# GS_02_Core.net
KiCad netlist of a schematic drawn in Altium Designer
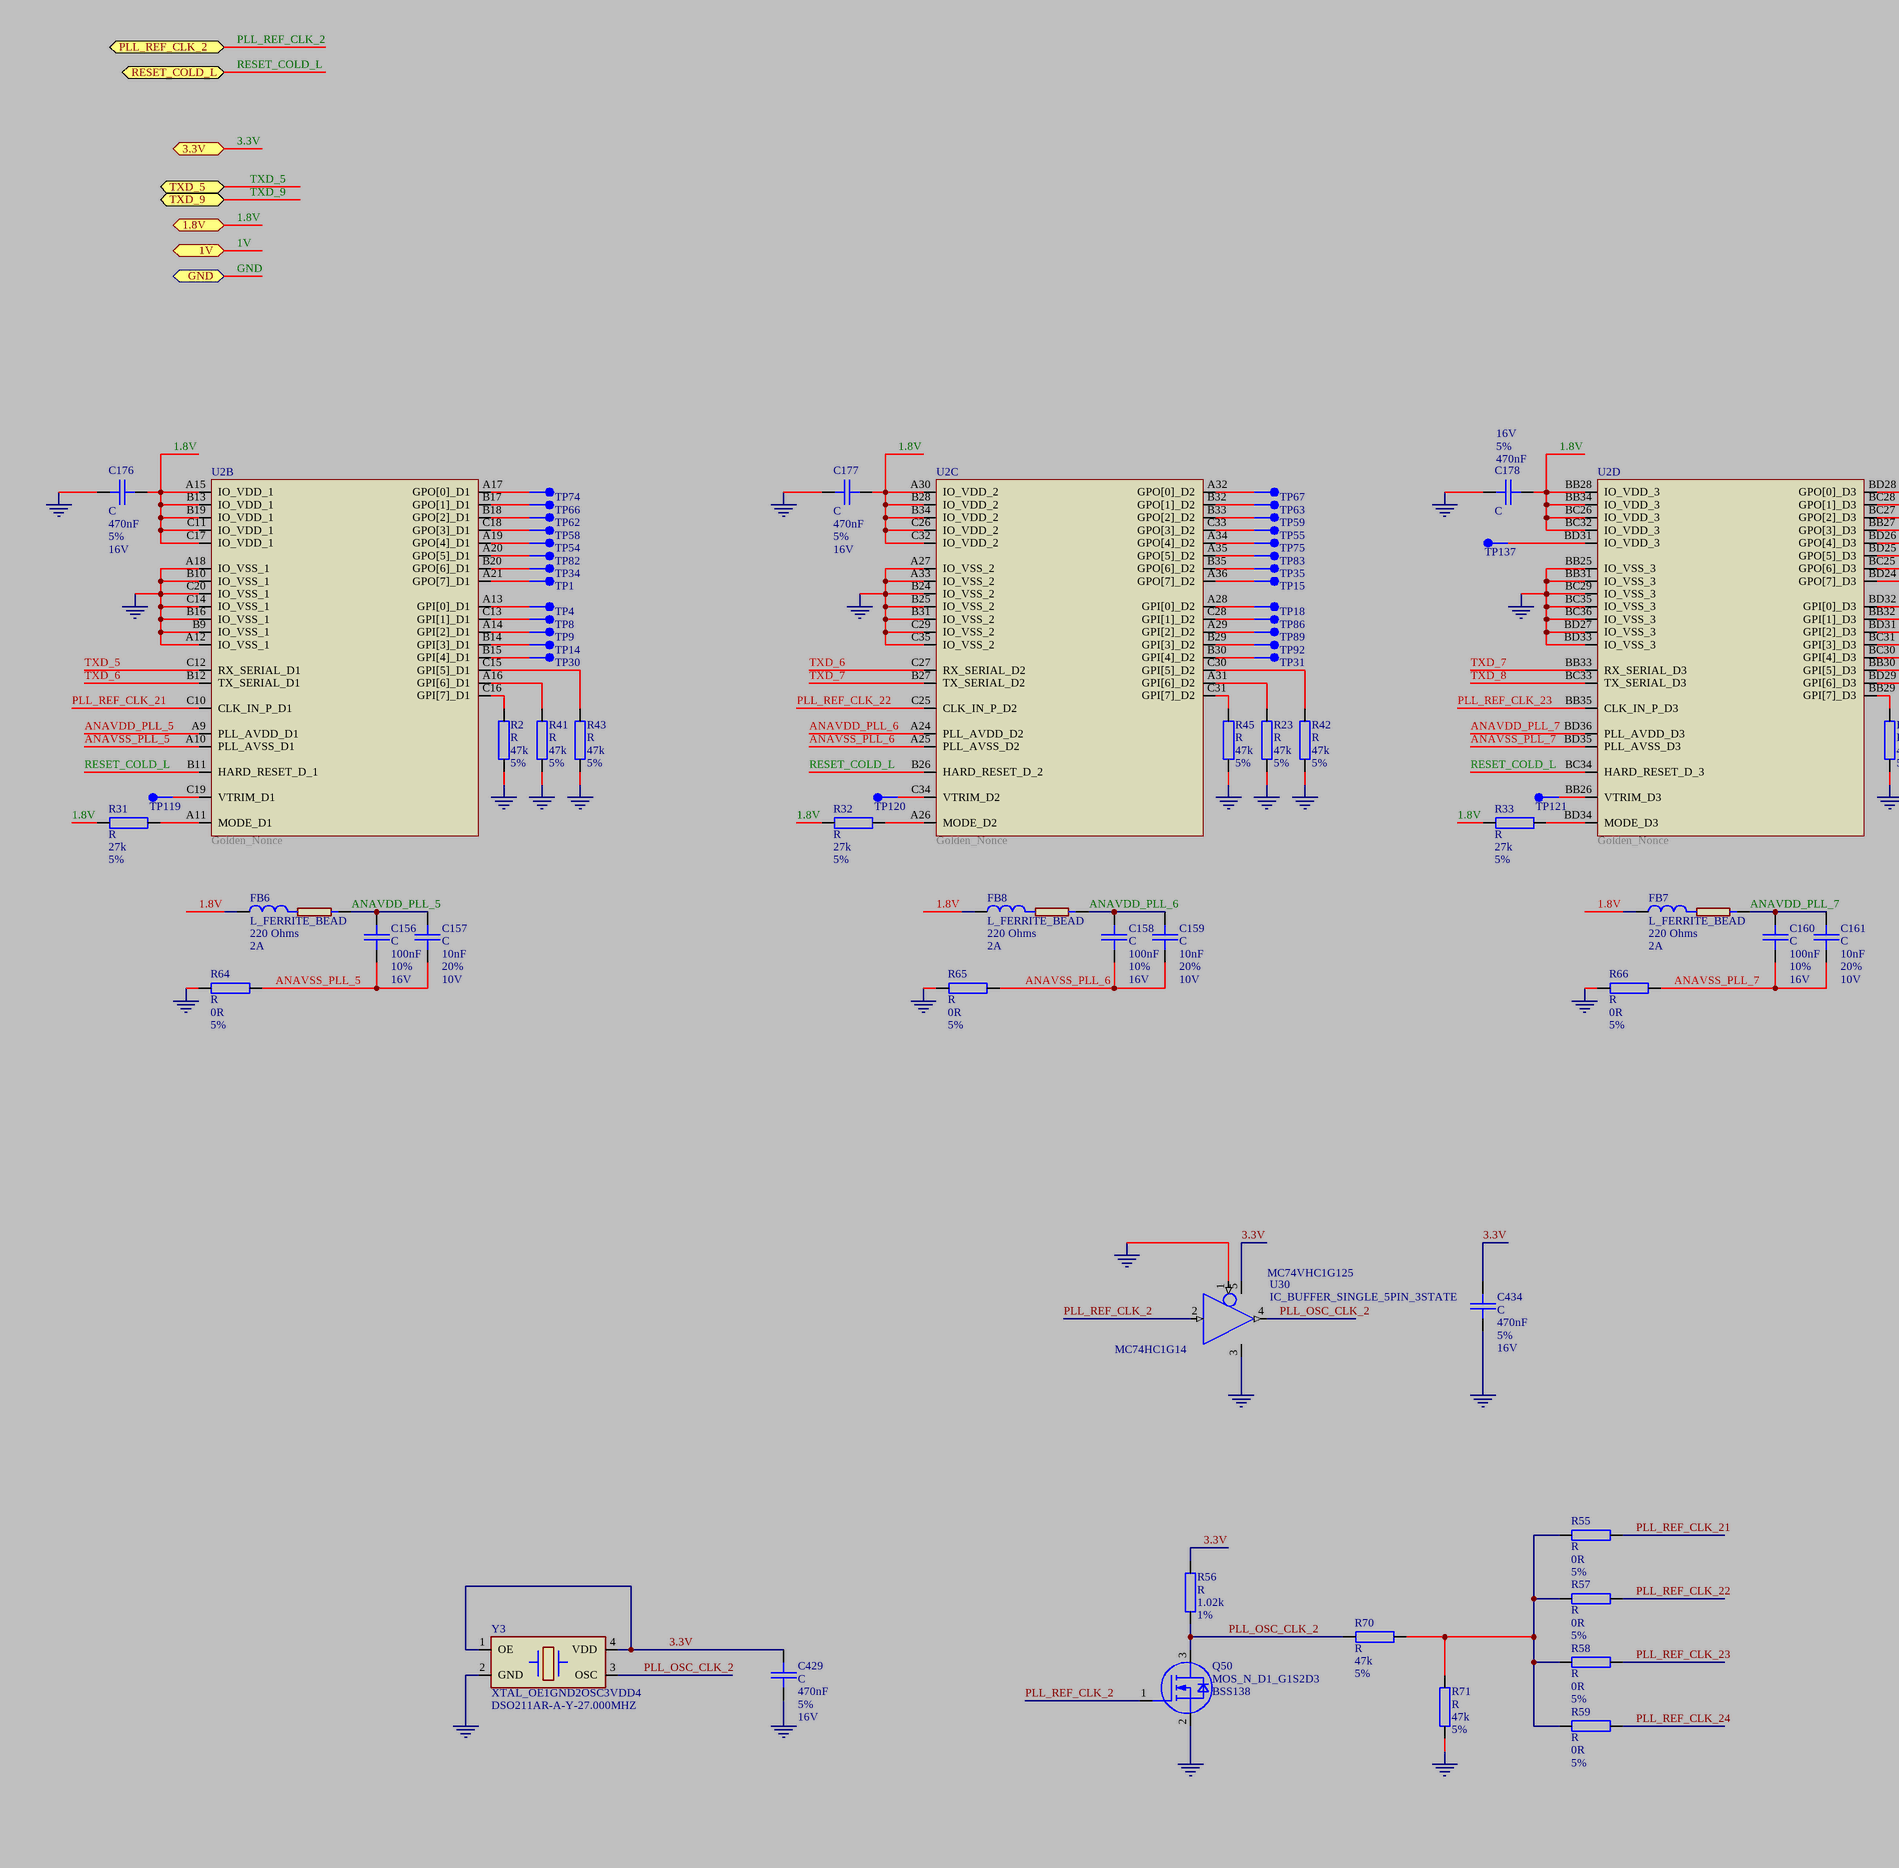
[diagram p0: GS_02_Core.SchDoc, left]
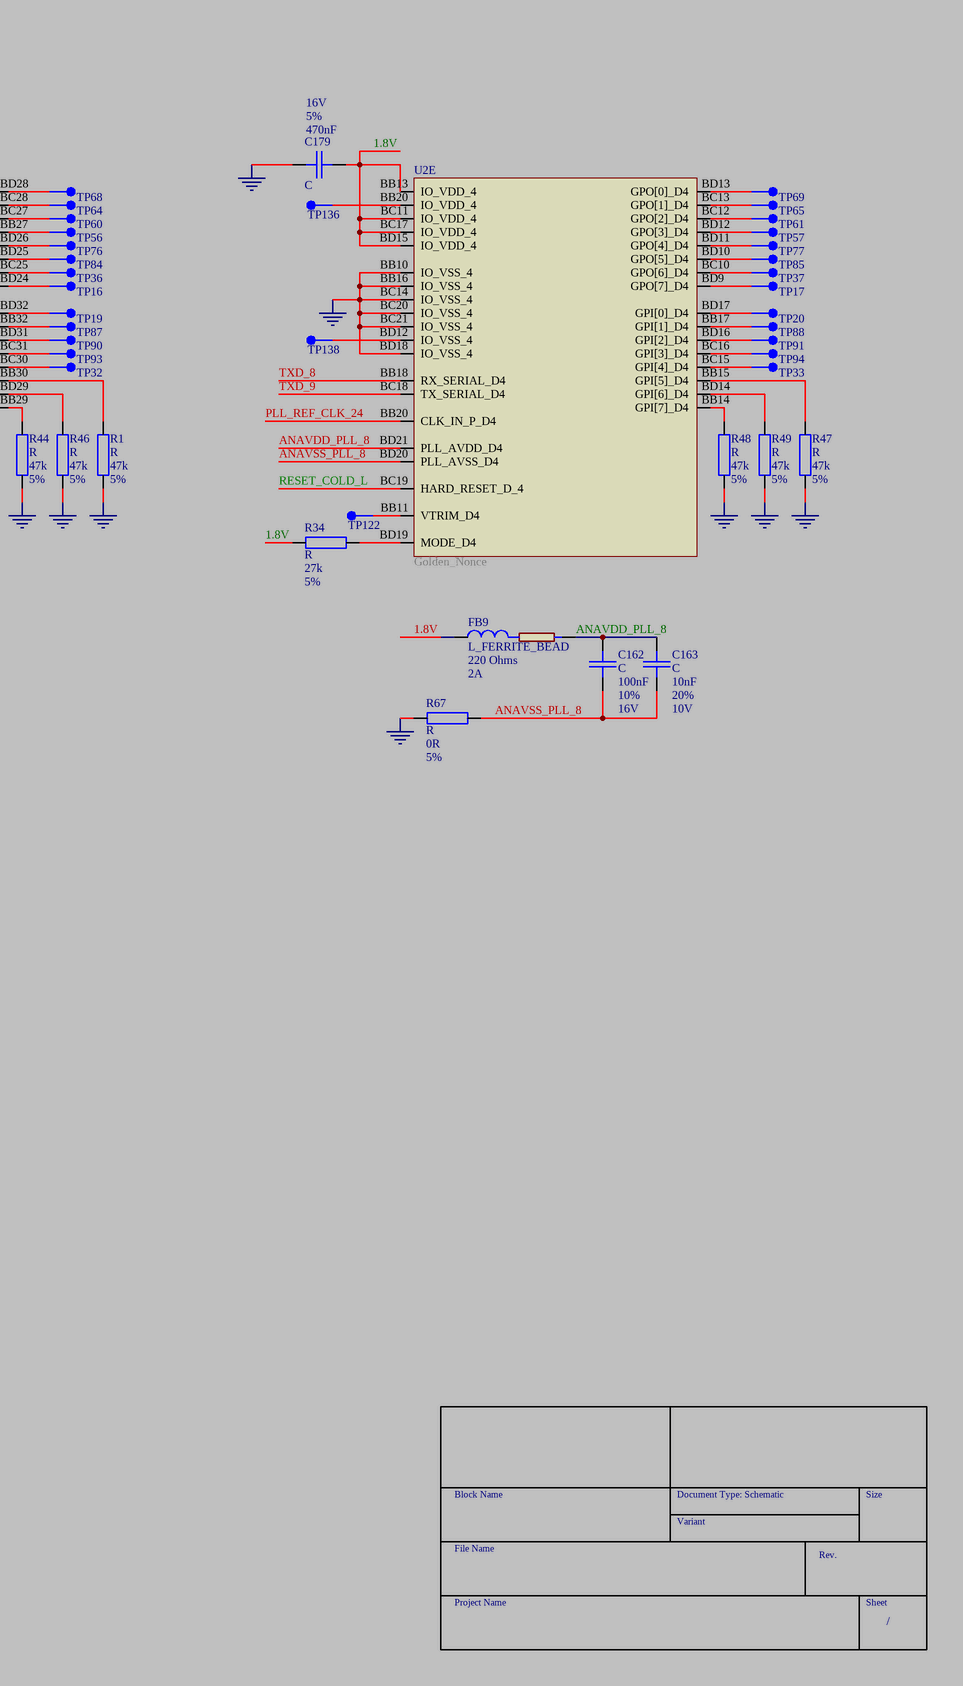
[diagram p1: GS_02_Core.SchDoc, right]

(export (version "E")
  (design (tool "Eeschema 10.0.6"))
  (components
    (comp (ref "C156")
      (value "C")
      (footprint "SMD_0603_CAPC1608X95N")
      (fields
        (field (name "DB_PART_NUMBER") "CAP000047357")
        (field (name "DB_VALUE") "100nF")
        (field (name "DB_TOLERANCE") "10%")
        (field (name "DB_VOLTAGE") "16V")
        (field (name "DB_MANUFACTURER_PART") "YAGEO      223878615649")
        (field (name "DB_APPROVED_BY") "VSN")
      )
      (libsource (lib "Database_Libs1") (part "C"))
    )
    (comp (ref "C157")
      (value "C")
      (footprint "SMD_0603_CAPC1608X95N")
      (fields
        (field (name "DB_PART_NUMBER") "CAP000038821")
        (field (name "DB_VALUE") "10nF")
        (field (name "DB_TOLERANCE") "20%")
        (field (name "DB_VOLTAGE") "10V")
        (field (name "DB_MANUFACTURER_PART") "KEMET    C0603C103M8GAC")
      )
      (libsource (lib "Database_Libs1") (part "C"))
    )
    (comp (ref "C158")
      (value "C")
      (footprint "SMD_0603_CAPC1608X95N")
      (fields
        (field (name "DB_PART_NUMBER") "CAP000047357")
        (field (name "DB_VALUE") "100nF")
        (field (name "DB_TOLERANCE") "10%")
        (field (name "DB_VOLTAGE") "16V")
        (field (name "DB_MANUFACTURER_PART") "YAGEO      223878615649")
        (field (name "DB_APPROVED_BY") "VSN")
      )
      (libsource (lib "Database_Libs1") (part "C"))
    )
    (comp (ref "C159")
      (value "C")
      (footprint "SMD_0603_CAPC1608X95N")
      (fields
        (field (name "DB_PART_NUMBER") "CAP000038821")
        (field (name "DB_VALUE") "10nF")
        (field (name "DB_TOLERANCE") "20%")
        (field (name "DB_VOLTAGE") "10V")
        (field (name "DB_MANUFACTURER_PART") "KEMET    C0603C103M8GAC")
      )
      (libsource (lib "Database_Libs1") (part "C"))
    )
    (comp (ref "C160")
      (value "C")
      (footprint "SMD_0603_CAPC1608X95N")
      (fields
        (field (name "DB_PART_NUMBER") "CAP000047357")
        (field (name "DB_VALUE") "100nF")
        (field (name "DB_TOLERANCE") "10%")
        (field (name "DB_VOLTAGE") "16V")
        (field (name "DB_MANUFACTURER_PART") "YAGEO      223878615649")
        (field (name "DB_APPROVED_BY") "VSN")
      )
      (libsource (lib "Database_Libs1") (part "C"))
    )
    (comp (ref "C161")
      (value "C")
      (footprint "SMD_0603_CAPC1608X95N")
      (fields
        (field (name "DB_PART_NUMBER") "CAP000038821")
        (field (name "DB_VALUE") "10nF")
        (field (name "DB_TOLERANCE") "20%")
        (field (name "DB_VOLTAGE") "10V")
        (field (name "DB_MANUFACTURER_PART") "KEMET    C0603C103M8GAC")
      )
      (libsource (lib "Database_Libs1") (part "C"))
    )
    (comp (ref "C162")
      (value "C")
      (footprint "SMD_0603_CAPC1608X95N")
      (fields
        (field (name "DB_PART_NUMBER") "CAP000047357")
        (field (name "DB_VALUE") "100nF")
        (field (name "DB_TOLERANCE") "10%")
        (field (name "DB_VOLTAGE") "16V")
        (field (name "DB_MANUFACTURER_PART") "YAGEO      223878615649")
        (field (name "DB_APPROVED_BY") "VSN")
      )
      (libsource (lib "Database_Libs1") (part "C"))
    )
    (comp (ref "C163")
      (value "C")
      (footprint "SMD_0603_CAPC1608X95N")
      (fields
        (field (name "DB_PART_NUMBER") "CAP000038821")
        (field (name "DB_VALUE") "10nF")
        (field (name "DB_TOLERANCE") "20%")
        (field (name "DB_VOLTAGE") "10V")
        (field (name "DB_MANUFACTURER_PART") "KEMET    C0603C103M8GAC")
      )
      (libsource (lib "Database_Libs1") (part "C"))
    )
    (comp (ref "C176")
      (value "C")
      (footprint "SMD_0603_CAPC1608X95N")
      (fields
        (field (name "DB_PART_NUMBER") "CAP000028169")
        (field (name "DB_VALUE") "470nF")
        (field (name "DB_TOLERANCE") "5%")
        (field (name "DB_VOLTAGE") "16V")
        (field (name "DB_MANUFACTURER_PART") "KEMET    C0603C474J4RAC")
      )
      (libsource (lib "Database_Libs1") (part "C"))
    )
    (comp (ref "C177")
      (value "C")
      (footprint "SMD_0603_CAPC1608X95N")
      (fields
        (field (name "DB_PART_NUMBER") "CAP000028169")
        (field (name "DB_VALUE") "470nF")
        (field (name "DB_TOLERANCE") "5%")
        (field (name "DB_VOLTAGE") "16V")
        (field (name "DB_MANUFACTURER_PART") "KEMET    C0603C474J4RAC")
      )
      (libsource (lib "Database_Libs1") (part "C"))
    )
    (comp (ref "C178")
      (value "C")
      (footprint "SMD_0603_CAPC1608X95N")
      (fields
        (field (name "DB_PART_NUMBER") "CAP000028169")
        (field (name "DB_VALUE") "470nF")
        (field (name "DB_TOLERANCE") "5%")
        (field (name "DB_VOLTAGE") "16V")
        (field (name "DB_MANUFACTURER_PART") "KEMET    C0603C474J4RAC")
      )
      (libsource (lib "Database_Libs1") (part "C"))
    )
    (comp (ref "C179")
      (value "C")
      (footprint "SMD_0603_CAPC1608X95N")
      (fields
        (field (name "DB_PART_NUMBER") "CAP000028169")
        (field (name "DB_VALUE") "470nF")
        (field (name "DB_TOLERANCE") "5%")
        (field (name "DB_VOLTAGE") "16V")
        (field (name "DB_MANUFACTURER_PART") "KEMET    C0603C474J4RAC")
      )
      (libsource (lib "Database_Libs1") (part "C"))
    )
    (comp (ref "C429")
      (value "C")
      (footprint "SMD_0603_CAPC1608X95N")
      (fields
        (field (name "DB_PART_NUMBER") "CAP000028169")
        (field (name "DB_VALUE") "470nF")
        (field (name "DB_TOLERANCE") "5%")
        (field (name "DB_VOLTAGE") "16V")
        (field (name "DB_MANUFACTURER_PART") "KEMET    C0603C474J4RAC")
      )
      (libsource (lib "Database_Libs1") (part "C"))
    )
    (comp (ref "C434")
      (value "C")
      (footprint "SMD_0603_CAPC1608X95N")
      (fields
        (field (name "DB_PART_NUMBER") "CAP000028169")
        (field (name "DB_VALUE") "470nF")
        (field (name "DB_TOLERANCE") "5%")
        (field (name "DB_VOLTAGE") "16V")
        (field (name "DB_MANUFACTURER_PART") "KEMET    C0603C474J4RAC")
      )
      (libsource (lib "Database_Libs1") (part "C"))
    )
    (comp (ref "FB6")
      (value "L_FERRITE_BEAD")
      (footprint "SMD_0805_INDC2012X105N")
      (fields
        (field (name "DB_PART_NUMBER") "IND000000029")
        (field (name "DB_VALUE") "220 Ohms")
        (field (name "DB_CURRENT") "2A")
        (field (name "DB_MANUFACTURER_PART") "MURATA       BLM21PG221SN1D")
        (field (name "DB_APPROVED_BY") "VSN")
      )
      (libsource (lib "Database_Libs1") (part "L_FERRITE_BEAD"))
    )
    (comp (ref "FB7")
      (value "L_FERRITE_BEAD")
      (footprint "SMD_0805_INDC2012X105N")
      (fields
        (field (name "DB_PART_NUMBER") "IND000000029")
        (field (name "DB_VALUE") "220 Ohms")
        (field (name "DB_CURRENT") "2A")
        (field (name "DB_MANUFACTURER_PART") "MURATA       BLM21PG221SN1D")
        (field (name "DB_APPROVED_BY") "VSN")
      )
      (libsource (lib "Database_Libs1") (part "L_FERRITE_BEAD"))
    )
    (comp (ref "FB8")
      (value "L_FERRITE_BEAD")
      (footprint "SMD_0805_INDC2012X105N")
      (fields
        (field (name "DB_PART_NUMBER") "IND000000029")
        (field (name "DB_VALUE") "220 Ohms")
        (field (name "DB_CURRENT") "2A")
        (field (name "DB_MANUFACTURER_PART") "MURATA       BLM21PG221SN1D")
        (field (name "DB_APPROVED_BY") "VSN")
      )
      (libsource (lib "Database_Libs1") (part "L_FERRITE_BEAD"))
    )
    (comp (ref "FB9")
      (value "L_FERRITE_BEAD")
      (footprint "SMD_0805_INDC2012X105N")
      (fields
        (field (name "DB_PART_NUMBER") "IND000000029")
        (field (name "DB_VALUE") "220 Ohms")
        (field (name "DB_CURRENT") "2A")
        (field (name "DB_MANUFACTURER_PART") "MURATA       BLM21PG221SN1D")
        (field (name "DB_APPROVED_BY") "VSN")
      )
      (libsource (lib "Database_Libs1") (part "L_FERRITE_BEAD"))
    )
    (comp (ref "Q50")
      (value "MOS_N_D1_G1S2D3")
      (footprint "SMD_SOT23_SOT95P240X112-3N")
      (fields
        (field (name "DB_PART_NUMBER") "TRA000001460")
        (field (name "DB_VALUE") "BSS138")
        (field (name "DB_MANUFACTURER_PART") "FAIRCHILD        BSS138LT1G")
        (field (name "DB_APPROVED_BY") "VSN")
      )
      (libsource (lib "Database_Libs1") (part "MOS_N_D1_G1S2D3"))
    )
    (comp (ref "R1")
      (value "R")
      (footprint "SMD_0603_RESC1608X55N")
      (fields
        (field (name "DB_PART_NUMBER") "RES000006462")
        (field (name "DB_VALUE") "47k")
        (field (name "DB_TOLERANCE") "5%")
        (field (name "DB_MANUFACTURER_PART") "YAGEO    RC0603JR-0747K")
      )
      (libsource (lib "Database_Libs1") (part "R"))
    )
    (comp (ref "R2")
      (value "R")
      (footprint "SMD_0603_RESC1608X55N")
      (fields
        (field (name "DB_PART_NUMBER") "RES000006462")
        (field (name "DB_VALUE") "47k")
        (field (name "DB_TOLERANCE") "5%")
        (field (name "DB_MANUFACTURER_PART") "YAGEO    RC0603JR-0747K")
      )
      (libsource (lib "Database_Libs1") (part "R"))
    )
    (comp (ref "R23")
      (value "R")
      (footprint "SMD_0603_RESC1608X55N")
      (fields
        (field (name "DB_PART_NUMBER") "RES000006462")
        (field (name "DB_VALUE") "47k")
        (field (name "DB_TOLERANCE") "5%")
        (field (name "DB_MANUFACTURER_PART") "YAGEO    RC0603JR-0747K")
      )
      (libsource (lib "Database_Libs1") (part "R"))
    )
    (comp (ref "R31")
      (value "R")
      (footprint "SMD_0603_RESC1608X55N")
      (fields
        (field (name "DB_PART_NUMBER") "RES000006456")
        (field (name "DB_VALUE") "27k")
        (field (name "DB_TOLERANCE") "5%")
        (field (name "DB_MANUFACTURER_PART") "YAGEO    RC0603JR-0727K")
      )
      (libsource (lib "Database_Libs1") (part "R"))
    )
    (comp (ref "R32")
      (value "R")
      (footprint "SMD_0603_RESC1608X55N")
      (fields
        (field (name "DB_PART_NUMBER") "RES000006456")
        (field (name "DB_VALUE") "27k")
        (field (name "DB_TOLERANCE") "5%")
        (field (name "DB_MANUFACTURER_PART") "YAGEO    RC0603JR-0727K")
      )
      (libsource (lib "Database_Libs1") (part "R"))
    )
    (comp (ref "R33")
      (value "R")
      (footprint "SMD_0603_RESC1608X55N")
      (fields
        (field (name "DB_PART_NUMBER") "RES000006456")
        (field (name "DB_VALUE") "27k")
        (field (name "DB_TOLERANCE") "5%")
        (field (name "DB_MANUFACTURER_PART") "YAGEO    RC0603JR-0727K")
      )
      (libsource (lib "Database_Libs1") (part "R"))
    )
    (comp (ref "R34")
      (value "R")
      (footprint "SMD_0603_RESC1608X55N")
      (fields
        (field (name "DB_PART_NUMBER") "RES000006456")
        (field (name "DB_VALUE") "27k")
        (field (name "DB_TOLERANCE") "5%")
        (field (name "DB_MANUFACTURER_PART") "YAGEO    RC0603JR-0727K")
      )
      (libsource (lib "Database_Libs1") (part "R"))
    )
    (comp (ref "R41")
      (value "R")
      (footprint "SMD_0603_RESC1608X55N")
      (fields
        (field (name "DB_PART_NUMBER") "RES000006462")
        (field (name "DB_VALUE") "47k")
        (field (name "DB_TOLERANCE") "5%")
        (field (name "DB_MANUFACTURER_PART") "YAGEO    RC0603JR-0747K")
      )
      (libsource (lib "Database_Libs1") (part "R"))
    )
    (comp (ref "R42")
      (value "R")
      (footprint "SMD_0603_RESC1608X55N")
      (fields
        (field (name "DB_PART_NUMBER") "RES000006462")
        (field (name "DB_VALUE") "47k")
        (field (name "DB_TOLERANCE") "5%")
        (field (name "DB_MANUFACTURER_PART") "YAGEO    RC0603JR-0747K")
      )
      (libsource (lib "Database_Libs1") (part "R"))
    )
    (comp (ref "R43")
      (value "R")
      (footprint "SMD_0603_RESC1608X55N")
      (fields
        (field (name "DB_PART_NUMBER") "RES000006462")
        (field (name "DB_VALUE") "47k")
        (field (name "DB_TOLERANCE") "5%")
        (field (name "DB_MANUFACTURER_PART") "YAGEO    RC0603JR-0747K")
      )
      (libsource (lib "Database_Libs1") (part "R"))
    )
    (comp (ref "R44")
      (value "R")
      (footprint "SMD_0603_RESC1608X55N")
      (fields
        (field (name "DB_PART_NUMBER") "RES000006462")
        (field (name "DB_VALUE") "47k")
        (field (name "DB_TOLERANCE") "5%")
        (field (name "DB_MANUFACTURER_PART") "YAGEO    RC0603JR-0747K")
      )
      (libsource (lib "Database_Libs1") (part "R"))
    )
    (comp (ref "R45")
      (value "R")
      (footprint "SMD_0603_RESC1608X55N")
      (fields
        (field (name "DB_PART_NUMBER") "RES000006462")
        (field (name "DB_VALUE") "47k")
        (field (name "DB_TOLERANCE") "5%")
        (field (name "DB_MANUFACTURER_PART") "YAGEO    RC0603JR-0747K")
      )
      (libsource (lib "Database_Libs1") (part "R"))
    )
    (comp (ref "R46")
      (value "R")
      (footprint "SMD_0603_RESC1608X55N")
      (fields
        (field (name "DB_PART_NUMBER") "RES000006462")
        (field (name "DB_VALUE") "47k")
        (field (name "DB_TOLERANCE") "5%")
        (field (name "DB_MANUFACTURER_PART") "YAGEO    RC0603JR-0747K")
      )
      (libsource (lib "Database_Libs1") (part "R"))
    )
    (comp (ref "R47")
      (value "R")
      (footprint "SMD_0603_RESC1608X55N")
      (fields
        (field (name "DB_PART_NUMBER") "RES000006462")
        (field (name "DB_VALUE") "47k")
        (field (name "DB_TOLERANCE") "5%")
        (field (name "DB_MANUFACTURER_PART") "YAGEO    RC0603JR-0747K")
      )
      (libsource (lib "Database_Libs1") (part "R"))
    )
    (comp (ref "R48")
      (value "R")
      (footprint "SMD_0603_RESC1608X55N")
      (fields
        (field (name "DB_PART_NUMBER") "RES000006462")
        (field (name "DB_VALUE") "47k")
        (field (name "DB_TOLERANCE") "5%")
        (field (name "DB_MANUFACTURER_PART") "YAGEO    RC0603JR-0747K")
      )
      (libsource (lib "Database_Libs1") (part "R"))
    )
    (comp (ref "R49")
      (value "R")
      (footprint "SMD_0603_RESC1608X55N")
      (fields
        (field (name "DB_PART_NUMBER") "RES000006462")
        (field (name "DB_VALUE") "47k")
        (field (name "DB_TOLERANCE") "5%")
        (field (name "DB_MANUFACTURER_PART") "YAGEO    RC0603JR-0747K")
      )
      (libsource (lib "Database_Libs1") (part "R"))
    )
    (comp (ref "R55")
      (value "R")
      (footprint "SMD_0603_RESC1608X55N")
      (fields
        (field (name "DB_PART_NUMBER") "RES000006349")
        (field (name "DB_VALUE") "0R")
        (field (name "DB_TOLERANCE") "5%")
        (field (name "DB_MANUFACTURER_PART") "YAGEO    RC0603JR-070R")
      )
      (libsource (lib "Database_Libs1") (part "R"))
    )
    (comp (ref "R56")
      (value "R")
      (footprint "SMD_0603_RESC1608X55N")
      (fields
        (field (name "DB_PART_NUMBER") "RES000001446")
        (field (name "DB_VALUE") "1.02k")
        (field (name "DB_TOLERANCE") "1%")
        (field (name "DB_MANUFACTURER_PART") "YAGEO    RC0603FR-071K02")
      )
      (libsource (lib "Database_Libs1") (part "R"))
    )
    (comp (ref "R57")
      (value "R")
      (footprint "SMD_0603_RESC1608X55N")
      (fields
        (field (name "DB_PART_NUMBER") "RES000006349")
        (field (name "DB_VALUE") "0R")
        (field (name "DB_TOLERANCE") "5%")
        (field (name "DB_MANUFACTURER_PART") "YAGEO    RC0603JR-070R")
      )
      (libsource (lib "Database_Libs1") (part "R"))
    )
    (comp (ref "R58")
      (value "R")
      (footprint "SMD_0603_RESC1608X55N")
      (fields
        (field (name "DB_PART_NUMBER") "RES000006349")
        (field (name "DB_VALUE") "0R")
        (field (name "DB_TOLERANCE") "5%")
        (field (name "DB_MANUFACTURER_PART") "YAGEO    RC0603JR-070R")
      )
      (libsource (lib "Database_Libs1") (part "R"))
    )
    (comp (ref "R59")
      (value "R")
      (footprint "SMD_0603_RESC1608X55N")
      (fields
        (field (name "DB_PART_NUMBER") "RES000006349")
        (field (name "DB_VALUE") "0R")
        (field (name "DB_TOLERANCE") "5%")
        (field (name "DB_MANUFACTURER_PART") "YAGEO    RC0603JR-070R")
      )
      (libsource (lib "Database_Libs1") (part "R"))
    )
    (comp (ref "R64")
      (value "R")
      (footprint "SMD_0402_RESC1005X37N")
      (fields
        (field (name "DB_PART_NUMBER") "RES000006002")
        (field (name "DB_VALUE") "0R")
        (field (name "DB_TOLERANCE") "5%")
        (field (name "DB_MANUFACTURER_PART") "YAGEO    RC0402JR-070R")
      )
      (libsource (lib "Database_Libs1") (part "R"))
    )
    (comp (ref "R65")
      (value "R")
      (footprint "SMD_0402_RESC1005X37N")
      (fields
        (field (name "DB_PART_NUMBER") "RES000006002")
        (field (name "DB_VALUE") "0R")
        (field (name "DB_TOLERANCE") "5%")
        (field (name "DB_MANUFACTURER_PART") "YAGEO    RC0402JR-070R")
      )
      (libsource (lib "Database_Libs1") (part "R"))
    )
    (comp (ref "R66")
      (value "R")
      (footprint "SMD_0402_RESC1005X37N")
      (fields
        (field (name "DB_PART_NUMBER") "RES000006002")
        (field (name "DB_VALUE") "0R")
        (field (name "DB_TOLERANCE") "5%")
        (field (name "DB_MANUFACTURER_PART") "YAGEO    RC0402JR-070R")
      )
      (libsource (lib "Database_Libs1") (part "R"))
    )
    (comp (ref "R67")
      (value "R")
      (footprint "SMD_0402_RESC1005X37N")
      (fields
        (field (name "DB_PART_NUMBER") "RES000006002")
        (field (name "DB_VALUE") "0R")
        (field (name "DB_TOLERANCE") "5%")
        (field (name "DB_MANUFACTURER_PART") "YAGEO    RC0402JR-070R")
      )
      (libsource (lib "Database_Libs1") (part "R"))
    )
    (comp (ref "R70")
      (value "R")
      (footprint "SMD_0603_RESC1608X55N")
      (fields
        (field (name "DB_PART_NUMBER") "RES000006462")
        (field (name "DB_VALUE") "47k")
        (field (name "DB_TOLERANCE") "5%")
        (field (name "DB_MANUFACTURER_PART") "YAGEO    RC0603JR-0747K")
      )
      (libsource (lib "Database_Libs1") (part "R"))
    )
    (comp (ref "R71")
      (value "R")
      (footprint "SMD_0603_RESC1608X55N")
      (fields
        (field (name "DB_PART_NUMBER") "RES000006462")
        (field (name "DB_VALUE") "47k")
        (field (name "DB_TOLERANCE") "5%")
        (field (name "DB_MANUFACTURER_PART") "YAGEO    RC0603JR-0747K")
      )
      (libsource (lib "Database_Libs1") (part "R"))
    )
    (comp (ref "TP1")
      (value "TEST_POINT_1")
      (footprint "SMD_TP_100-254")
      (fields (field (name "DB_PART_NUMBER") "TPO000000001"))
      (libsource (lib "Database_Libs1") (part "TEST_POINT_1"))
    )
    (comp (ref "TP4")
      (value "TEST_POINT_1")
      (footprint "SMD_TP_100-254")
      (fields (field (name "DB_PART_NUMBER") "TPO000000001"))
      (libsource (lib "Database_Libs1") (part "TEST_POINT_1"))
    )
    (comp (ref "TP8")
      (value "TEST_POINT_1")
      (footprint "SMD_TP_100-254")
      (fields (field (name "DB_PART_NUMBER") "TPO000000001"))
      (libsource (lib "Database_Libs1") (part "TEST_POINT_1"))
    )
    (comp (ref "TP9")
      (value "TEST_POINT_1")
      (footprint "SMD_TP_100-254")
      (fields (field (name "DB_PART_NUMBER") "TPO000000001"))
      (libsource (lib "Database_Libs1") (part "TEST_POINT_1"))
    )
    (comp (ref "TP14")
      (value "TEST_POINT_1")
      (footprint "SMD_TP_100-254")
      (fields (field (name "DB_PART_NUMBER") "TPO000000001"))
      (libsource (lib "Database_Libs1") (part "TEST_POINT_1"))
    )
    (comp (ref "TP15")
      (value "TEST_POINT_1")
      (footprint "SMD_TP_100-254")
      (fields (field (name "DB_PART_NUMBER") "TPO000000001"))
      (libsource (lib "Database_Libs1") (part "TEST_POINT_1"))
    )
    (comp (ref "TP16")
      (value "TEST_POINT_1")
      (footprint "SMD_TP_100-254")
      (fields (field (name "DB_PART_NUMBER") "TPO000000001"))
      (libsource (lib "Database_Libs1") (part "TEST_POINT_1"))
    )
    (comp (ref "TP17")
      (value "TEST_POINT_1")
      (footprint "SMD_TP_100-254")
      (fields (field (name "DB_PART_NUMBER") "TPO000000001"))
      (libsource (lib "Database_Libs1") (part "TEST_POINT_1"))
    )
    (comp (ref "TP18")
      (value "TEST_POINT_1")
      (footprint "SMD_TP_100-254")
      (fields (field (name "DB_PART_NUMBER") "TPO000000001"))
      (libsource (lib "Database_Libs1") (part "TEST_POINT_1"))
    )
    (comp (ref "TP19")
      (value "TEST_POINT_1")
      (footprint "SMD_TP_100-254")
      (fields (field (name "DB_PART_NUMBER") "TPO000000001"))
      (libsource (lib "Database_Libs1") (part "TEST_POINT_1"))
    )
    (comp (ref "TP20")
      (value "TEST_POINT_1")
      (footprint "SMD_TP_100-254")
      (fields (field (name "DB_PART_NUMBER") "TPO000000001"))
      (libsource (lib "Database_Libs1") (part "TEST_POINT_1"))
    )
    (comp (ref "TP30")
      (value "TEST_POINT_1")
      (footprint "SMD_TP_100-254")
      (fields (field (name "DB_PART_NUMBER") "TPO000000001"))
      (libsource (lib "Database_Libs1") (part "TEST_POINT_1"))
    )
    (comp (ref "TP31")
      (value "TEST_POINT_1")
      (footprint "SMD_TP_100-254")
      (fields (field (name "DB_PART_NUMBER") "TPO000000001"))
      (libsource (lib "Database_Libs1") (part "TEST_POINT_1"))
    )
    (comp (ref "TP32")
      (value "TEST_POINT_1")
      (footprint "SMD_TP_100-254")
      (fields (field (name "DB_PART_NUMBER") "TPO000000001"))
      (libsource (lib "Database_Libs1") (part "TEST_POINT_1"))
    )
    (comp (ref "TP33")
      (value "TEST_POINT_1")
      (footprint "SMD_TP_100-254")
      (fields (field (name "DB_PART_NUMBER") "TPO000000001"))
      (libsource (lib "Database_Libs1") (part "TEST_POINT_1"))
    )
    (comp (ref "TP34")
      (value "TEST_POINT_1")
      (footprint "SMD_TP_100-254")
      (fields (field (name "DB_PART_NUMBER") "TPO000000001"))
      (libsource (lib "Database_Libs1") (part "TEST_POINT_1"))
    )
    (comp (ref "TP35")
      (value "TEST_POINT_1")
      (footprint "SMD_TP_100-254")
      (fields (field (name "DB_PART_NUMBER") "TPO000000001"))
      (libsource (lib "Database_Libs1") (part "TEST_POINT_1"))
    )
    (comp (ref "TP36")
      (value "TEST_POINT_1")
      (footprint "SMD_TP_100-254")
      (fields (field (name "DB_PART_NUMBER") "TPO000000001"))
      (libsource (lib "Database_Libs1") (part "TEST_POINT_1"))
    )
    (comp (ref "TP37")
      (value "TEST_POINT_1")
      (footprint "SMD_TP_100-254")
      (fields (field (name "DB_PART_NUMBER") "TPO000000001"))
      (libsource (lib "Database_Libs1") (part "TEST_POINT_1"))
    )
    (comp (ref "TP54")
      (value "TEST_POINT_1")
      (footprint "SMD_TP_100-254")
      (fields (field (name "DB_PART_NUMBER") "TPO000000001"))
      (libsource (lib "Database_Libs1") (part "TEST_POINT_1"))
    )
    (comp (ref "TP55")
      (value "TEST_POINT_1")
      (footprint "SMD_TP_100-254")
      (fields (field (name "DB_PART_NUMBER") "TPO000000001"))
      (libsource (lib "Database_Libs1") (part "TEST_POINT_1"))
    )
    (comp (ref "TP56")
      (value "TEST_POINT_1")
      (footprint "SMD_TP_100-254")
      (fields (field (name "DB_PART_NUMBER") "TPO000000001"))
      (libsource (lib "Database_Libs1") (part "TEST_POINT_1"))
    )
    (comp (ref "TP57")
      (value "TEST_POINT_1")
      (footprint "SMD_TP_100-254")
      (fields (field (name "DB_PART_NUMBER") "TPO000000001"))
      (libsource (lib "Database_Libs1") (part "TEST_POINT_1"))
    )
    (comp (ref "TP58")
      (value "TEST_POINT_1")
      (footprint "SMD_TP_100-254")
      (fields (field (name "DB_PART_NUMBER") "TPO000000001"))
      (libsource (lib "Database_Libs1") (part "TEST_POINT_1"))
    )
    (comp (ref "TP59")
      (value "TEST_POINT_1")
      (footprint "SMD_TP_100-254")
      (fields (field (name "DB_PART_NUMBER") "TPO000000001"))
      (libsource (lib "Database_Libs1") (part "TEST_POINT_1"))
    )
    (comp (ref "TP60")
      (value "TEST_POINT_1")
      (footprint "SMD_TP_100-254")
      (fields (field (name "DB_PART_NUMBER") "TPO000000001"))
      (libsource (lib "Database_Libs1") (part "TEST_POINT_1"))
    )
    (comp (ref "TP61")
      (value "TEST_POINT_1")
      (footprint "SMD_TP_100-254")
      (fields (field (name "DB_PART_NUMBER") "TPO000000001"))
      (libsource (lib "Database_Libs1") (part "TEST_POINT_1"))
    )
    (comp (ref "TP62")
      (value "TEST_POINT_1")
      (footprint "SMD_TP_100-254")
      (fields (field (name "DB_PART_NUMBER") "TPO000000001"))
      (libsource (lib "Database_Libs1") (part "TEST_POINT_1"))
    )
    (comp (ref "TP63")
      (value "TEST_POINT_1")
      (footprint "SMD_TP_100-254")
      (fields (field (name "DB_PART_NUMBER") "TPO000000001"))
      (libsource (lib "Database_Libs1") (part "TEST_POINT_1"))
    )
    (comp (ref "TP64")
      (value "TEST_POINT_1")
      (footprint "SMD_TP_100-254")
      (fields (field (name "DB_PART_NUMBER") "TPO000000001"))
      (libsource (lib "Database_Libs1") (part "TEST_POINT_1"))
    )
    (comp (ref "TP65")
      (value "TEST_POINT_1")
      (footprint "SMD_TP_100-254")
      (fields (field (name "DB_PART_NUMBER") "TPO000000001"))
      (libsource (lib "Database_Libs1") (part "TEST_POINT_1"))
    )
    (comp (ref "TP66")
      (value "TEST_POINT_1")
      (footprint "SMD_TP_100-254")
      (fields (field (name "DB_PART_NUMBER") "TPO000000001"))
      (libsource (lib "Database_Libs1") (part "TEST_POINT_1"))
    )
    (comp (ref "TP67")
      (value "TEST_POINT_1")
      (footprint "SMD_TP_100-254")
      (fields (field (name "DB_PART_NUMBER") "TPO000000001"))
      (libsource (lib "Database_Libs1") (part "TEST_POINT_1"))
    )
    (comp (ref "TP68")
      (value "TEST_POINT_1")
      (footprint "SMD_TP_100-254")
      (fields (field (name "DB_PART_NUMBER") "TPO000000001"))
      (libsource (lib "Database_Libs1") (part "TEST_POINT_1"))
    )
    (comp (ref "TP69")
      (value "TEST_POINT_1")
      (footprint "SMD_TP_100-254")
      (fields (field (name "DB_PART_NUMBER") "TPO000000001"))
      (libsource (lib "Database_Libs1") (part "TEST_POINT_1"))
    )
    (comp (ref "TP74")
      (value "TEST_POINT_1")
      (footprint "SMD_TP_100-254")
      (fields (field (name "DB_PART_NUMBER") "TPO000000001"))
      (libsource (lib "Database_Libs1") (part "TEST_POINT_1"))
    )
    (comp (ref "TP75")
      (value "TEST_POINT_1")
      (footprint "SMD_TP_100-254")
      (fields (field (name "DB_PART_NUMBER") "TPO000000001"))
      (libsource (lib "Database_Libs1") (part "TEST_POINT_1"))
    )
    (comp (ref "TP76")
      (value "TEST_POINT_1")
      (footprint "SMD_TP_100-254")
      (fields (field (name "DB_PART_NUMBER") "TPO000000001"))
      (libsource (lib "Database_Libs1") (part "TEST_POINT_1"))
    )
    (comp (ref "TP77")
      (value "TEST_POINT_1")
      (footprint "SMD_TP_100-254")
      (fields (field (name "DB_PART_NUMBER") "TPO000000001"))
      (libsource (lib "Database_Libs1") (part "TEST_POINT_1"))
    )
    (comp (ref "TP82")
      (value "TEST_POINT_1")
      (footprint "SMD_TP_100-254")
      (fields (field (name "DB_PART_NUMBER") "TPO000000001"))
      (libsource (lib "Database_Libs1") (part "TEST_POINT_1"))
    )
    (comp (ref "TP83")
      (value "TEST_POINT_1")
      (footprint "SMD_TP_100-254")
      (fields (field (name "DB_PART_NUMBER") "TPO000000001"))
      (libsource (lib "Database_Libs1") (part "TEST_POINT_1"))
    )
    (comp (ref "TP84")
      (value "TEST_POINT_1")
      (footprint "SMD_TP_100-254")
      (fields (field (name "DB_PART_NUMBER") "TPO000000001"))
      (libsource (lib "Database_Libs1") (part "TEST_POINT_1"))
    )
    (comp (ref "TP85")
      (value "TEST_POINT_1")
      (footprint "SMD_TP_100-254")
      (fields (field (name "DB_PART_NUMBER") "TPO000000001"))
      (libsource (lib "Database_Libs1") (part "TEST_POINT_1"))
    )
    (comp (ref "TP86")
      (value "TEST_POINT_1")
      (footprint "SMD_TP_100-254")
      (fields (field (name "DB_PART_NUMBER") "TPO000000001"))
      (libsource (lib "Database_Libs1") (part "TEST_POINT_1"))
    )
    (comp (ref "TP87")
      (value "TEST_POINT_1")
      (footprint "SMD_TP_100-254")
      (fields (field (name "DB_PART_NUMBER") "TPO000000001"))
      (libsource (lib "Database_Libs1") (part "TEST_POINT_1"))
    )
    (comp (ref "TP88")
      (value "TEST_POINT_1")
      (footprint "SMD_TP_100-254")
      (fields (field (name "DB_PART_NUMBER") "TPO000000001"))
      (libsource (lib "Database_Libs1") (part "TEST_POINT_1"))
    )
    (comp (ref "TP89")
      (value "TEST_POINT_1")
      (footprint "SMD_TP_100-254")
      (fields (field (name "DB_PART_NUMBER") "TPO000000001"))
      (libsource (lib "Database_Libs1") (part "TEST_POINT_1"))
    )
    (comp (ref "TP90")
      (value "TEST_POINT_1")
      (footprint "SMD_TP_100-254")
      (fields (field (name "DB_PART_NUMBER") "TPO000000001"))
      (libsource (lib "Database_Libs1") (part "TEST_POINT_1"))
    )
    (comp (ref "TP91")
      (value "TEST_POINT_1")
      (footprint "SMD_TP_100-254")
      (fields (field (name "DB_PART_NUMBER") "TPO000000001"))
      (libsource (lib "Database_Libs1") (part "TEST_POINT_1"))
    )
    (comp (ref "TP92")
      (value "TEST_POINT_1")
      (footprint "SMD_TP_100-254")
      (fields (field (name "DB_PART_NUMBER") "TPO000000001"))
      (libsource (lib "Database_Libs1") (part "TEST_POINT_1"))
    )
    (comp (ref "TP93")
      (value "TEST_POINT_1")
      (footprint "SMD_TP_100-254")
      (fields (field (name "DB_PART_NUMBER") "TPO000000001"))
      (libsource (lib "Database_Libs1") (part "TEST_POINT_1"))
    )
    (comp (ref "TP94")
      (value "TEST_POINT_1")
      (footprint "SMD_TP_100-254")
      (fields (field (name "DB_PART_NUMBER") "TPO000000001"))
      (libsource (lib "Database_Libs1") (part "TEST_POINT_1"))
    )
    (comp (ref "TP119")
      (value "TEST_POINT_1")
      (footprint "SMD_TP_100-254")
      (fields (field (name "DB_PART_NUMBER") "TPO000000001"))
      (libsource (lib "Database_Libs1") (part "TEST_POINT_1"))
    )
    (comp (ref "TP120")
      (value "TEST_POINT_1")
      (footprint "SMD_TP_100-254")
      (fields (field (name "DB_PART_NUMBER") "TPO000000001"))
      (libsource (lib "Database_Libs1") (part "TEST_POINT_1"))
    )
    (comp (ref "TP121")
      (value "TEST_POINT_1")
      (footprint "SMD_TP_100-254")
      (fields (field (name "DB_PART_NUMBER") "TPO000000001"))
      (libsource (lib "Database_Libs1") (part "TEST_POINT_1"))
    )
    (comp (ref "TP122")
      (value "TEST_POINT_1")
      (footprint "SMD_TP_100-254")
      (fields (field (name "DB_PART_NUMBER") "TPO000000001"))
      (libsource (lib "Database_Libs1") (part "TEST_POINT_1"))
    )
    (comp (ref "TP136")
      (value "TEST_POINT_1")
      (footprint "SMD_TP_100-254")
      (fields (field (name "DB_PART_NUMBER") "TPO000000001"))
      (libsource (lib "Database_Libs1") (part "TEST_POINT_1"))
    )
    (comp (ref "TP137")
      (value "TEST_POINT_1")
      (footprint "SMD_TP_100-254")
      (fields (field (name "DB_PART_NUMBER") "TPO000000001"))
      (libsource (lib "Database_Libs1") (part "TEST_POINT_1"))
    )
    (comp (ref "TP138")
      (value "TEST_POINT_1")
      (footprint "SMD_TP_100-254")
      (fields (field (name "DB_PART_NUMBER") "TPO000000001"))
      (libsource (lib "Database_Libs1") (part "TEST_POINT_1"))
    )
    (comp (ref "U2") (value "Golden_Nonce") (libsource (lib "Schlib1") (part "Golden_Nonce")))
    (comp (ref "U30")
      (value "IC_BUFFER_SINGLE_5PIN_3STATE")
      (footprint "SMD_SOT95P280X110-5N")
      (fields
        (field (name "DB_PART_NUMBER") "DIG000000005")
        (field (name "DB_VALUE") "MC74VHC1G125")
        (field (name "DB_MANUFACTURER_PART") "ON Semiconductor       M74VHC1G125DTT1G")
        (field (name "DB_APPROVED_BY") "VSN")
      )
      (libsource (lib "Database_Libs1") (part "IC_BUFFER_SINGLE_5PIN_3STATE"))
    )
    (comp (ref "Y3")
      (value "XTAL_OE1GND2OSC3VDD4")
      (footprint "SMD_OSCCC500X700X100-4N")
      (fields
        (field (name "DB_PART_NUMBER") "OSC000000015")
        (field (name "DB_VALUE") "DSO211AR-A-Y-27.000MHZ")
        (field (name "DB_MANUFACTURER_PART") "KDS DAISHINKU      DSO211AR-A-Y-27.000MHZ")
        (field (name "DB_APPROVED_BY") "VSN")
      )
      (libsource (lib "Database_Libs1") (part "XTAL_OE1GND2OSC3VDD4"))
    )
  )
  (nets
    (net (code "1") (name "/1.8V") (class "Default")
      (node (ref "C176") (pin "2") (pinfunction "2_2") (pintype "passive"))
      (node (ref "C177") (pin "2") (pinfunction "2_2") (pintype "passive"))
      (node (ref "C178") (pin "2") (pinfunction "2_2") (pintype "passive"))
      (node (ref "C179") (pin "2") (pinfunction "2_2") (pintype "passive"))
      (node (ref "FB6") (pin "1") (pinfunction "1_1") (pintype "passive"))
      (node (ref "FB7") (pin "1") (pinfunction "1_1") (pintype "passive"))
      (node (ref "FB8") (pin "1") (pinfunction "1_1") (pintype "passive"))
      (node (ref "FB9") (pin "1") (pinfunction "1_1") (pintype "passive"))
      (node (ref "R31") (pin "1") (pinfunction "1_1") (pintype "passive"))
      (node (ref "R32") (pin "1") (pinfunction "1_1") (pintype "passive"))
      (node (ref "R33") (pin "1") (pinfunction "1_1") (pintype "passive"))
      (node (ref "R34") (pin "1") (pinfunction "1_1") (pintype "passive"))
      (node (ref "U2") (pin "A15") (pinfunction "IO_VDD_1_A15") (pintype "passive"))
      (node (ref "U2") (pin "A30") (pinfunction "IO_VDD_2_A30") (pintype "passive"))
      (node (ref "U2") (pin "B13") (pinfunction "IO_VDD_1_B13") (pintype "passive"))
      (node (ref "U2") (pin "B19") (pinfunction "IO_VDD_1_B19") (pintype "passive"))
      (node (ref "U2") (pin "B28") (pinfunction "IO_VDD_2_B28") (pintype "passive"))
      (node (ref "U2") (pin "B34") (pinfunction "IO_VDD_2_B34") (pintype "passive"))
      (node (ref "U2") (pin "BB13") (pinfunction "IO_VDD_4_BB13") (pintype "passive"))
      (node (ref "U2") (pin "BB28") (pinfunction "IO_VDD_3_BB28") (pintype "passive"))
      (node (ref "U2") (pin "BB34") (pinfunction "IO_VDD_3_BB34") (pintype "passive"))
      (node (ref "U2") (pin "BC11") (pinfunction "IO_VDD_4_BC11") (pintype "passive"))
      (node (ref "U2") (pin "BC17") (pinfunction "IO_VDD_4_BC17") (pintype "passive"))
      (node (ref "U2") (pin "BC26") (pinfunction "IO_VDD_3_BC26") (pintype "passive"))
      (node (ref "U2") (pin "BC32") (pinfunction "IO_VDD_3_BC32") (pintype "passive"))
      (node (ref "U2") (pin "BD15") (pinfunction "IO_VDD_4_BD15") (pintype "passive"))
      (node (ref "U2") (pin "C11") (pinfunction "IO_VDD_1_C11") (pintype "passive"))
      (node (ref "U2") (pin "C17") (pinfunction "IO_VDD_1_C17") (pintype "passive"))
      (node (ref "U2") (pin "C26") (pinfunction "IO_VDD_2_C26") (pintype "passive"))
      (node (ref "U2") (pin "C32") (pinfunction "IO_VDD_2_C32") (pintype "passive"))
    )
    (net (code "3") (name "/3.3V") (class "Default")
      (node (ref "C429") (pin "2") (pinfunction "2_2") (pintype "passive"))
      (node (ref "C434") (pin "2") (pinfunction "2_2") (pintype "passive"))
      (node (ref "R56") (pin "1") (pinfunction "1_1") (pintype "passive"))
      (node (ref "U30") (pin "5") (pinfunction "VCC_5") (pintype "power_in"))
      (node (ref "Y3") (pin "1") (pinfunction "OE_1") (pintype "passive"))
      (node (ref "Y3") (pin "4") (pinfunction "VDD_4") (pintype "passive"))
    )
    (net (code "4") (name "/ANAVDD_PLL_5") (class "Default")
      (node (ref "C156") (pin "1") (pinfunction "1_1") (pintype "passive"))
      (node (ref "C157") (pin "1") (pinfunction "1_1") (pintype "passive"))
      (node (ref "FB6") (pin "2") (pinfunction "2_2") (pintype "passive"))
      (node (ref "U2") (pin "A9") (pinfunction "PLL_AVDD_D1_A9") (pintype "passive"))
    )
    (net (code "5") (name "/ANAVDD_PLL_6") (class "Default")
      (node (ref "C158") (pin "1") (pinfunction "1_1") (pintype "passive"))
      (node (ref "C159") (pin "1") (pinfunction "1_1") (pintype "passive"))
      (node (ref "FB8") (pin "2") (pinfunction "2_2") (pintype "passive"))
      (node (ref "U2") (pin "A24") (pinfunction "PLL_AVDD_D2_A24") (pintype "passive"))
    )
    (net (code "6") (name "/ANAVDD_PLL_7") (class "Default")
      (node (ref "C160") (pin "1") (pinfunction "1_1") (pintype "passive"))
      (node (ref "C161") (pin "1") (pinfunction "1_1") (pintype "passive"))
      (node (ref "FB7") (pin "2") (pinfunction "2_2") (pintype "passive"))
      (node (ref "U2") (pin "BD36") (pinfunction "PLL_AVDD_D3_BD36") (pintype "passive"))
    )
    (net (code "7") (name "/ANAVDD_PLL_8") (class "Default")
      (node (ref "C162") (pin "1") (pinfunction "1_1") (pintype "passive"))
      (node (ref "C163") (pin "1") (pinfunction "1_1") (pintype "passive"))
      (node (ref "FB9") (pin "2") (pinfunction "2_2") (pintype "passive"))
      (node (ref "U2") (pin "BD21") (pinfunction "PLL_AVDD_D4_BD21") (pintype "passive"))
    )
    (net (code "8") (name "/ANAVSS_PLL_5") (class "Default")
      (node (ref "C156") (pin "2") (pinfunction "2_2") (pintype "passive"))
      (node (ref "C157") (pin "2") (pinfunction "2_2") (pintype "passive"))
      (node (ref "R64") (pin "2") (pinfunction "2_2") (pintype "passive"))
      (node (ref "U2") (pin "A10") (pinfunction "PLL_AVSS_D1_A10") (pintype "passive"))
    )
    (net (code "9") (name "/ANAVSS_PLL_6") (class "Default")
      (node (ref "C158") (pin "2") (pinfunction "2_2") (pintype "passive"))
      (node (ref "C159") (pin "2") (pinfunction "2_2") (pintype "passive"))
      (node (ref "R65") (pin "2") (pinfunction "2_2") (pintype "passive"))
      (node (ref "U2") (pin "A25") (pinfunction "PLL_AVSS_D2_A25") (pintype "passive"))
    )
    (net (code "10") (name "/ANAVSS_PLL_7") (class "Default")
      (node (ref "C160") (pin "2") (pinfunction "2_2") (pintype "passive"))
      (node (ref "C161") (pin "2") (pinfunction "2_2") (pintype "passive"))
      (node (ref "R66") (pin "2") (pinfunction "2_2") (pintype "passive"))
      (node (ref "U2") (pin "BD35") (pinfunction "PLL_AVSS_D3_BD35") (pintype "passive"))
    )
    (net (code "11") (name "/ANAVSS_PLL_8") (class "Default")
      (node (ref "C162") (pin "2") (pinfunction "2_2") (pintype "passive"))
      (node (ref "C163") (pin "2") (pinfunction "2_2") (pintype "passive"))
      (node (ref "R67") (pin "2") (pinfunction "2_2") (pintype "passive"))
      (node (ref "U2") (pin "BD20") (pinfunction "PLL_AVSS_D4_BD20") (pintype "passive"))
    )
    (net (code "12") (name "/PLL_OSC_CLK_2") (class "Default")
      (node (ref "Q50") (pin "3") (pinfunction "D_3") (pintype "passive"))
      (node (ref "R56") (pin "2") (pinfunction "2_2") (pintype "passive"))
      (node (ref "R70") (pin "1") (pinfunction "1_1") (pintype "passive"))
      (node (ref "U30") (pin "4") (pinfunction "OUTY_4") (pintype "output"))
      (node (ref "Y3") (pin "3") (pinfunction "OSC_3") (pintype "passive"))
    )
    (net (code "13") (name "/PLL_REF_CLK_2") (class "Default")
      (node (ref "Q50") (pin "1") (pinfunction "G_1") (pintype "passive"))
      (node (ref "U30") (pin "2") (pinfunction "INA_2") (pintype "input"))
    )
    (net (code "14") (name "/PLL_REF_CLK_21") (class "Default")
      (node (ref "R55") (pin "2") (pinfunction "2_2") (pintype "passive"))
      (node (ref "U2") (pin "C10") (pinfunction "CLK_IN_P_D1_C10") (pintype "passive"))
    )
    (net (code "15") (name "/PLL_REF_CLK_22") (class "Default")
      (node (ref "R57") (pin "2") (pinfunction "2_2") (pintype "passive"))
      (node (ref "U2") (pin "C25") (pinfunction "CLK_IN_P_D2_C25") (pintype "passive"))
    )
    (net (code "16") (name "/PLL_REF_CLK_23") (class "Default")
      (node (ref "R58") (pin "2") (pinfunction "2_2") (pintype "passive"))
      (node (ref "U2") (pin "BB35") (pinfunction "CLK_IN_P_D3_BB35") (pintype "passive"))
    )
    (net (code "17") (name "/PLL_REF_CLK_24") (class "Default")
      (node (ref "R59") (pin "2") (pinfunction "2_2") (pintype "passive"))
      (node (ref "U2") (pin "BB20") (pinfunction "CLK_IN_P_D4_BB20") (pintype "passive"))
    )
    (net (code "18") (name "/RESET_COLD_L") (class "Default")
      (node (ref "U2") (pin "B11") (pinfunction "HARD_RESET_D_1_B11") (pintype "passive"))
      (node (ref "U2") (pin "B26") (pinfunction "HARD_RESET_D_2_B26") (pintype "passive"))
      (node (ref "U2") (pin "BC19") (pinfunction "HARD_RESET_D_4_BC19") (pintype "passive"))
      (node (ref "U2") (pin "BC34") (pinfunction "HARD_RESET_D_3_BC34") (pintype "passive"))
    )
    (net (code "19") (name "/TXD_5") (class "Default")
      (node (ref "U2") (pin "C12") (pinfunction "RX_SERIAL_D1_C12") (pintype "passive"))
    )
    (net (code "20") (name "/TXD_6") (class "Default")
      (node (ref "U2") (pin "B12") (pinfunction "TX_SERIAL_D1_B12") (pintype "passive"))
      (node (ref "U2") (pin "C27") (pinfunction "RX_SERIAL_D2_C27") (pintype "passive"))
    )
    (net (code "21") (name "/TXD_7") (class "Default")
      (node (ref "U2") (pin "B27") (pinfunction "TX_SERIAL_D2_B27") (pintype "passive"))
      (node (ref "U2") (pin "BB33") (pinfunction "RX_SERIAL_D3_BB33") (pintype "passive"))
    )
    (net (code "22") (name "/TXD_8") (class "Default")
      (node (ref "U2") (pin "BB18") (pinfunction "RX_SERIAL_D4_BB18") (pintype "passive"))
      (node (ref "U2") (pin "BC33") (pinfunction "TX_SERIAL_D3_BC33") (pintype "passive"))
    )
    (net (code "23") (name "/TXD_9") (class "Default")
      (node (ref "U2") (pin "BC18") (pinfunction "TX_SERIAL_D4_BC18") (pintype "passive"))
    )
    (net (code "24") (name "GND") (class "Default")
      (node (ref "C176") (pin "1") (pinfunction "1_1") (pintype "passive"))
      (node (ref "C177") (pin "1") (pinfunction "1_1") (pintype "passive"))
      (node (ref "C178") (pin "1") (pinfunction "1_1") (pintype "passive"))
      (node (ref "C179") (pin "1") (pinfunction "1_1") (pintype "passive"))
      (node (ref "C429") (pin "1") (pinfunction "1_1") (pintype "passive"))
      (node (ref "C434") (pin "1") (pinfunction "1_1") (pintype "passive"))
      (node (ref "Q50") (pin "2") (pinfunction "S_2") (pintype "passive"))
      (node (ref "R1") (pin "2") (pinfunction "2_2") (pintype "passive"))
      (node (ref "R2") (pin "2") (pinfunction "2_2") (pintype "passive"))
      (node (ref "R23") (pin "2") (pinfunction "2_2") (pintype "passive"))
      (node (ref "R41") (pin "2") (pinfunction "2_2") (pintype "passive"))
      (node (ref "R42") (pin "2") (pinfunction "2_2") (pintype "passive"))
      (node (ref "R43") (pin "2") (pinfunction "2_2") (pintype "passive"))
      (node (ref "R44") (pin "2") (pinfunction "2_2") (pintype "passive"))
      (node (ref "R45") (pin "2") (pinfunction "2_2") (pintype "passive"))
      (node (ref "R46") (pin "2") (pinfunction "2_2") (pintype "passive"))
      (node (ref "R47") (pin "2") (pinfunction "2_2") (pintype "passive"))
      (node (ref "R48") (pin "2") (pinfunction "2_2") (pintype "passive"))
      (node (ref "R49") (pin "2") (pinfunction "2_2") (pintype "passive"))
      (node (ref "R64") (pin "1") (pinfunction "1_1") (pintype "passive"))
      (node (ref "R65") (pin "1") (pinfunction "1_1") (pintype "passive"))
      (node (ref "R66") (pin "1") (pinfunction "1_1") (pintype "passive"))
      (node (ref "R67") (pin "1") (pinfunction "1_1") (pintype "passive"))
      (node (ref "R71") (pin "2") (pinfunction "2_2") (pintype "passive"))
      (node (ref "U2") (pin "A12") (pinfunction "IO_VSS_1_A12") (pintype "passive"))
      (node (ref "U2") (pin "A18") (pinfunction "IO_VSS_1_A18") (pintype "passive"))
      (node (ref "U2") (pin "A27") (pinfunction "IO_VSS_2_A27") (pintype "passive"))
      (node (ref "U2") (pin "A33") (pinfunction "IO_VSS_2_A33") (pintype "passive"))
      (node (ref "U2") (pin "B10") (pinfunction "IO_VSS_1_B10") (pintype "passive"))
      (node (ref "U2") (pin "B16") (pinfunction "IO_VSS_1_B16") (pintype "passive"))
      (node (ref "U2") (pin "B24") (pinfunction "IO_VSS_2_B24") (pintype "passive"))
      (node (ref "U2") (pin "B25") (pinfunction "IO_VSS_2_B25") (pintype "passive"))
      (node (ref "U2") (pin "B31") (pinfunction "IO_VSS_2_B31") (pintype "passive"))
      (node (ref "U2") (pin "B9") (pinfunction "IO_VSS_1_B9") (pintype "passive"))
      (node (ref "U2") (pin "BB10") (pinfunction "IO_VSS_4_BB10") (pintype "passive"))
      (node (ref "U2") (pin "BB16") (pinfunction "IO_VSS_4_BB16") (pintype "passive"))
      (node (ref "U2") (pin "BB25") (pinfunction "IO_VSS_3_BB25") (pintype "passive"))
      (node (ref "U2") (pin "BB31") (pinfunction "IO_VSS_3_BB31") (pintype "passive"))
      (node (ref "U2") (pin "BC14") (pinfunction "IO_VSS_4_BC14") (pintype "passive"))
      (node (ref "U2") (pin "BC20") (pinfunction "IO_VSS_4_BC20") (pintype "passive"))
      (node (ref "U2") (pin "BC21") (pinfunction "IO_VSS_4_BC21") (pintype "passive"))
      (node (ref "U2") (pin "BC29") (pinfunction "IO_VSS_3_BC29") (pintype "passive"))
      (node (ref "U2") (pin "BC35") (pinfunction "IO_VSS_3_BC35") (pintype "passive"))
      (node (ref "U2") (pin "BC36") (pinfunction "IO_VSS_3_BC36") (pintype "passive"))
      (node (ref "U2") (pin "BD18") (pinfunction "IO_VSS_4_BD18") (pintype "passive"))
      (node (ref "U2") (pin "BD27") (pinfunction "IO_VSS_3_BD27") (pintype "passive"))
      (node (ref "U2") (pin "BD33") (pinfunction "IO_VSS_3_BD33") (pintype "passive"))
      (node (ref "U2") (pin "C14") (pinfunction "IO_VSS_1_C14") (pintype "passive"))
      (node (ref "U2") (pin "C20") (pinfunction "IO_VSS_1_C20") (pintype "passive"))
      (node (ref "U2") (pin "C29") (pinfunction "IO_VSS_2_C29") (pintype "passive"))
      (node (ref "U2") (pin "C35") (pinfunction "IO_VSS_2_C35") (pintype "passive"))
      (node (ref "U30") (pin "1") (pinfunction "~{OE}_1") (pintype "input"))
      (node (ref "U30") (pin "3") (pinfunction "GND_3") (pintype "power_in"))
      (node (ref "Y3") (pin "2") (pinfunction "GND_2") (pintype "passive"))
    )
    (net (code "25") (name "Net-(R55-Pad1)") (class "Default")
      (node (ref "R55") (pin "1") (pinfunction "1_1") (pintype "passive"))
      (node (ref "R57") (pin "1") (pinfunction "1_1") (pintype "passive"))
      (node (ref "R58") (pin "1") (pinfunction "1_1") (pintype "passive"))
      (node (ref "R59") (pin "1") (pinfunction "1_1") (pintype "passive"))
      (node (ref "R70") (pin "2") (pinfunction "2_2") (pintype "passive"))
      (node (ref "R71") (pin "1") (pinfunction "1_1") (pintype "passive"))
    )
    (net (code "26") (name "Net-(TP136-Pad1)") (class "Default")
      (node (ref "TP136") (pin "1") (pinfunction "1_1") (pintype "passive"))
      (node (ref "U2") (pin "BB20") (pinfunction "IO_VDD_4_BB20") (pintype "passive"))
    )
    (net (code "27") (name "Net-(TP137-Pad1)") (class "Default")
      (node (ref "TP137") (pin "1") (pinfunction "1_1") (pintype "passive"))
      (node (ref "U2") (pin "BD31") (pinfunction "IO_VDD_3_BD31") (pintype "passive"))
    )
    (net (code "28") (name "Net-(TP138-Pad1)") (class "Default")
      (node (ref "TP138") (pin "1") (pinfunction "1_1") (pintype "passive"))
      (node (ref "U2") (pin "BD12") (pinfunction "IO_VSS_4_BD12") (pintype "passive"))
    )
    (net (code "29") (name "Net-(U2B-GPI[0]_D1)") (class "Default")
      (node (ref "TP4") (pin "1") (pinfunction "1_1") (pintype "passive"))
      (node (ref "U2") (pin "A13") (pinfunction "GPI[0]_D1_A13") (pintype "passive"))
    )
    (net (code "30") (name "Net-(U2B-GPI[1]_D1)") (class "Default")
      (node (ref "TP8") (pin "1") (pinfunction "1_1") (pintype "passive"))
      (node (ref "U2") (pin "C13") (pinfunction "GPI[1]_D1_C13") (pintype "passive"))
    )
    (net (code "31") (name "Net-(U2B-GPI[2]_D1)") (class "Default")
      (node (ref "TP9") (pin "1") (pinfunction "1_1") (pintype "passive"))
      (node (ref "U2") (pin "A14") (pinfunction "GPI[2]_D1_A14") (pintype "passive"))
    )
    (net (code "32") (name "Net-(U2B-GPI[3]_D1)") (class "Default")
      (node (ref "TP14") (pin "1") (pinfunction "1_1") (pintype "passive"))
      (node (ref "U2") (pin "B14") (pinfunction "GPI[3]_D1_B14") (pintype "passive"))
    )
    (net (code "33") (name "Net-(U2B-GPI[4]_D1)") (class "Default")
      (node (ref "TP30") (pin "1") (pinfunction "1_1") (pintype "passive"))
      (node (ref "U2") (pin "B15") (pinfunction "GPI[4]_D1_B15") (pintype "passive"))
    )
    (net (code "34") (name "Net-(U2B-GPI[5]_D1)") (class "Default")
      (node (ref "R43") (pin "1") (pinfunction "1_1") (pintype "passive"))
      (node (ref "U2") (pin "C15") (pinfunction "GPI[5]_D1_C15") (pintype "passive"))
    )
    (net (code "35") (name "Net-(U2B-GPI[6]_D1)") (class "Default")
      (node (ref "R41") (pin "1") (pinfunction "1_1") (pintype "passive"))
      (node (ref "U2") (pin "A16") (pinfunction "GPI[6]_D1_A16") (pintype "passive"))
    )
    (net (code "36") (name "Net-(U2B-GPI[7]_D1)") (class "Default")
      (node (ref "R2") (pin "1") (pinfunction "1_1") (pintype "passive"))
      (node (ref "U2") (pin "C16") (pinfunction "GPI[7]_D1_C16") (pintype "passive"))
    )
    (net (code "37") (name "Net-(U2B-GPO[0]_D1)") (class "Default")
      (node (ref "TP74") (pin "1") (pinfunction "1_1") (pintype "passive"))
      (node (ref "U2") (pin "A17") (pinfunction "GPO[0]_D1_A17") (pintype "passive"))
    )
    (net (code "38") (name "Net-(U2B-GPO[1]_D1)") (class "Default")
      (node (ref "TP66") (pin "1") (pinfunction "1_1") (pintype "passive"))
      (node (ref "U2") (pin "B17") (pinfunction "GPO[1]_D1_B17") (pintype "passive"))
    )
    (net (code "39") (name "Net-(U2B-GPO[2]_D1)") (class "Default")
      (node (ref "TP62") (pin "1") (pinfunction "1_1") (pintype "passive"))
      (node (ref "U2") (pin "B18") (pinfunction "GPO[2]_D1_B18") (pintype "passive"))
    )
    (net (code "40") (name "Net-(U2B-GPO[3]_D1)") (class "Default")
      (node (ref "TP58") (pin "1") (pinfunction "1_1") (pintype "passive"))
      (node (ref "U2") (pin "C18") (pinfunction "GPO[3]_D1_C18") (pintype "passive"))
    )
    (net (code "41") (name "Net-(U2B-GPO[4]_D1)") (class "Default")
      (node (ref "TP54") (pin "1") (pinfunction "1_1") (pintype "passive"))
      (node (ref "U2") (pin "A19") (pinfunction "GPO[4]_D1_A19") (pintype "passive"))
    )
    (net (code "42") (name "Net-(U2B-GPO[5]_D1)") (class "Default")
      (node (ref "TP82") (pin "1") (pinfunction "1_1") (pintype "passive"))
      (node (ref "U2") (pin "A20") (pinfunction "GPO[5]_D1_A20") (pintype "passive"))
    )
    (net (code "43") (name "Net-(U2B-GPO[6]_D1)") (class "Default")
      (node (ref "TP34") (pin "1") (pinfunction "1_1") (pintype "passive"))
      (node (ref "U2") (pin "B20") (pinfunction "GPO[6]_D1_B20") (pintype "passive"))
    )
    (net (code "44") (name "Net-(U2B-GPO[7]_D1)") (class "Default")
      (node (ref "TP1") (pin "1") (pinfunction "1_1") (pintype "passive"))
      (node (ref "U2") (pin "A21") (pinfunction "GPO[7]_D1_A21") (pintype "passive"))
    )
    (net (code "45") (name "Net-(U2B-MODE_D1)") (class "Default")
      (node (ref "R31") (pin "2") (pinfunction "2_2") (pintype "passive"))
      (node (ref "U2") (pin "A11") (pinfunction "MODE_D1_A11") (pintype "passive"))
    )
    (net (code "46") (name "Net-(U2B-VTRIM_D1)") (class "Default")
      (node (ref "TP119") (pin "1") (pinfunction "1_1") (pintype "passive"))
      (node (ref "U2") (pin "C19") (pinfunction "VTRIM_D1_C19") (pintype "passive"))
    )
    (net (code "47") (name "Net-(U2C-GPI[0]_D2)") (class "Default")
      (node (ref "TP18") (pin "1") (pinfunction "1_1") (pintype "passive"))
      (node (ref "U2") (pin "A28") (pinfunction "GPI[0]_D2_A28") (pintype "passive"))
    )
    (net (code "48") (name "Net-(U2C-GPI[1]_D2)") (class "Default")
      (node (ref "TP86") (pin "1") (pinfunction "1_1") (pintype "passive"))
      (node (ref "U2") (pin "C28") (pinfunction "GPI[1]_D2_C28") (pintype "passive"))
    )
    (net (code "49") (name "Net-(U2C-GPI[2]_D2)") (class "Default")
      (node (ref "TP89") (pin "1") (pinfunction "1_1") (pintype "passive"))
      (node (ref "U2") (pin "A29") (pinfunction "GPI[2]_D2_A29") (pintype "passive"))
    )
    (net (code "50") (name "Net-(U2C-GPI[3]_D2)") (class "Default")
      (node (ref "TP92") (pin "1") (pinfunction "1_1") (pintype "passive"))
      (node (ref "U2") (pin "B29") (pinfunction "GPI[3]_D2_B29") (pintype "passive"))
    )
    (net (code "51") (name "Net-(U2C-GPI[4]_D2)") (class "Default")
      (node (ref "TP31") (pin "1") (pinfunction "1_1") (pintype "passive"))
      (node (ref "U2") (pin "B30") (pinfunction "GPI[4]_D2_B30") (pintype "passive"))
    )
    (net (code "52") (name "Net-(U2C-GPI[5]_D2)") (class "Default")
      (node (ref "R42") (pin "1") (pinfunction "1_1") (pintype "passive"))
      (node (ref "U2") (pin "C30") (pinfunction "GPI[5]_D2_C30") (pintype "passive"))
    )
    (net (code "53") (name "Net-(U2C-GPI[6]_D2)") (class "Default")
      (node (ref "R23") (pin "1") (pinfunction "1_1") (pintype "passive"))
      (node (ref "U2") (pin "A31") (pinfunction "GPI[6]_D2_A31") (pintype "passive"))
    )
    (net (code "54") (name "Net-(U2C-GPI[7]_D2)") (class "Default")
      (node (ref "R45") (pin "1") (pinfunction "1_1") (pintype "passive"))
      (node (ref "U2") (pin "C31") (pinfunction "GPI[7]_D2_C31") (pintype "passive"))
    )
    (net (code "55") (name "Net-(U2C-GPO[0]_D2)") (class "Default")
      (node (ref "TP67") (pin "1") (pinfunction "1_1") (pintype "passive"))
      (node (ref "U2") (pin "A32") (pinfunction "GPO[0]_D2_A32") (pintype "passive"))
    )
    (net (code "56") (name "Net-(U2C-GPO[1]_D2)") (class "Default")
      (node (ref "TP63") (pin "1") (pinfunction "1_1") (pintype "passive"))
      (node (ref "U2") (pin "B32") (pinfunction "GPO[1]_D2_B32") (pintype "passive"))
    )
    (net (code "57") (name "Net-(U2C-GPO[2]_D2)") (class "Default")
      (node (ref "TP59") (pin "1") (pinfunction "1_1") (pintype "passive"))
      (node (ref "U2") (pin "B33") (pinfunction "GPO[2]_D2_B33") (pintype "passive"))
    )
    (net (code "58") (name "Net-(U2C-GPO[3]_D2)") (class "Default")
      (node (ref "TP55") (pin "1") (pinfunction "1_1") (pintype "passive"))
      (node (ref "U2") (pin "C33") (pinfunction "GPO[3]_D2_C33") (pintype "passive"))
    )
    (net (code "59") (name "Net-(U2C-GPO[4]_D2)") (class "Default")
      (node (ref "TP75") (pin "1") (pinfunction "1_1") (pintype "passive"))
      (node (ref "U2") (pin "A34") (pinfunction "GPO[4]_D2_A34") (pintype "passive"))
    )
    (net (code "60") (name "Net-(U2C-GPO[5]_D2)") (class "Default")
      (node (ref "TP83") (pin "1") (pinfunction "1_1") (pintype "passive"))
      (node (ref "U2") (pin "A35") (pinfunction "GPO[5]_D2_A35") (pintype "passive"))
    )
    (net (code "61") (name "Net-(U2C-GPO[6]_D2)") (class "Default")
      (node (ref "TP35") (pin "1") (pinfunction "1_1") (pintype "passive"))
      (node (ref "U2") (pin "B35") (pinfunction "GPO[6]_D2_B35") (pintype "passive"))
    )
    (net (code "62") (name "Net-(U2C-GPO[7]_D2)") (class "Default")
      (node (ref "TP15") (pin "1") (pinfunction "1_1") (pintype "passive"))
      (node (ref "U2") (pin "A36") (pinfunction "GPO[7]_D2_A36") (pintype "passive"))
    )
    (net (code "63") (name "Net-(U2C-MODE_D2)") (class "Default")
      (node (ref "R32") (pin "2") (pinfunction "2_2") (pintype "passive"))
      (node (ref "U2") (pin "A26") (pinfunction "MODE_D2_A26") (pintype "passive"))
    )
    (net (code "64") (name "Net-(U2C-VTRIM_D2)") (class "Default")
      (node (ref "TP120") (pin "1") (pinfunction "1_1") (pintype "passive"))
      (node (ref "U2") (pin "C34") (pinfunction "VTRIM_D2_C34") (pintype "passive"))
    )
    (net (code "65") (name "Net-(U2D-GPI[0]_D3)") (class "Default")
      (node (ref "TP19") (pin "1") (pinfunction "1_1") (pintype "passive"))
      (node (ref "U2") (pin "BD32") (pinfunction "GPI[0]_D3_BD32") (pintype "passive"))
    )
    (net (code "66") (name "Net-(U2D-GPI[1]_D3)") (class "Default")
      (node (ref "TP87") (pin "1") (pinfunction "1_1") (pintype "passive"))
      (node (ref "U2") (pin "BB32") (pinfunction "GPI[1]_D3_BB32") (pintype "passive"))
    )
    (net (code "67") (name "Net-(U2D-GPI[2]_D3)") (class "Default")
      (node (ref "TP90") (pin "1") (pinfunction "1_1") (pintype "passive"))
      (node (ref "U2") (pin "BD31") (pinfunction "GPI[2]_D3_BD31") (pintype "passive"))
    )
    (net (code "68") (name "Net-(U2D-GPI[3]_D3)") (class "Default")
      (node (ref "TP93") (pin "1") (pinfunction "1_1") (pintype "passive"))
      (node (ref "U2") (pin "BC31") (pinfunction "GPI[3]_D3_BC31") (pintype "passive"))
    )
    (net (code "69") (name "Net-(U2D-GPI[4]_D3)") (class "Default")
      (node (ref "TP32") (pin "1") (pinfunction "1_1") (pintype "passive"))
      (node (ref "U2") (pin "BC30") (pinfunction "GPI[4]_D3_BC30") (pintype "passive"))
    )
    (net (code "70") (name "Net-(U2D-GPI[5]_D3)") (class "Default")
      (node (ref "R1") (pin "1") (pinfunction "1_1") (pintype "passive"))
      (node (ref "U2") (pin "BB30") (pinfunction "GPI[5]_D3_BB30") (pintype "passive"))
    )
    (net (code "71") (name "Net-(U2D-GPI[6]_D3)") (class "Default")
      (node (ref "R46") (pin "1") (pinfunction "1_1") (pintype "passive"))
      (node (ref "U2") (pin "BD29") (pinfunction "GPI[6]_D3_BD29") (pintype "passive"))
    )
    (net (code "72") (name "Net-(U2D-GPI[7]_D3)") (class "Default")
      (node (ref "R44") (pin "1") (pinfunction "1_1") (pintype "passive"))
      (node (ref "U2") (pin "BB29") (pinfunction "GPI[7]_D3_BB29") (pintype "passive"))
    )
    (net (code "73") (name "Net-(U2D-GPO[0]_D3)") (class "Default")
      (node (ref "TP68") (pin "1") (pinfunction "1_1") (pintype "passive"))
      (node (ref "U2") (pin "BD28") (pinfunction "GPO[0]_D3_BD28") (pintype "passive"))
    )
    (net (code "74") (name "Net-(U2D-GPO[1]_D3)") (class "Default")
      (node (ref "TP64") (pin "1") (pinfunction "1_1") (pintype "passive"))
      (node (ref "U2") (pin "BC28") (pinfunction "GPO[1]_D3_BC28") (pintype "passive"))
    )
    (net (code "75") (name "Net-(U2D-GPO[2]_D3)") (class "Default")
      (node (ref "TP60") (pin "1") (pinfunction "1_1") (pintype "passive"))
      (node (ref "U2") (pin "BC27") (pinfunction "GPO[2]_D3_BC27") (pintype "passive"))
    )
    (net (code "76") (name "Net-(U2D-GPO[3]_D3)") (class "Default")
      (node (ref "TP56") (pin "1") (pinfunction "1_1") (pintype "passive"))
      (node (ref "U2") (pin "BB27") (pinfunction "GPO[3]_D3_BB27") (pintype "passive"))
    )
    (net (code "77") (name "Net-(U2D-GPO[4]_D3)") (class "Default")
      (node (ref "TP76") (pin "1") (pinfunction "1_1") (pintype "passive"))
      (node (ref "U2") (pin "BD26") (pinfunction "GPO[4]_D3_BD26") (pintype "passive"))
    )
    (net (code "78") (name "Net-(U2D-GPO[5]_D3)") (class "Default")
      (node (ref "TP84") (pin "1") (pinfunction "1_1") (pintype "passive"))
      (node (ref "U2") (pin "BD25") (pinfunction "GPO[5]_D3_BD25") (pintype "passive"))
    )
    (net (code "79") (name "Net-(U2D-GPO[6]_D3)") (class "Default")
      (node (ref "TP36") (pin "1") (pinfunction "1_1") (pintype "passive"))
      (node (ref "U2") (pin "BC25") (pinfunction "GPO[6]_D3_BC25") (pintype "passive"))
    )
    (net (code "80") (name "Net-(U2D-GPO[7]_D3)") (class "Default")
      (node (ref "TP16") (pin "1") (pinfunction "1_1") (pintype "passive"))
      (node (ref "U2") (pin "BD24") (pinfunction "GPO[7]_D3_BD24") (pintype "passive"))
    )
    (net (code "81") (name "Net-(U2D-MODE_D3)") (class "Default")
      (node (ref "R33") (pin "2") (pinfunction "2_2") (pintype "passive"))
      (node (ref "U2") (pin "BD34") (pinfunction "MODE_D3_BD34") (pintype "passive"))
    )
    (net (code "82") (name "Net-(U2D-VTRIM_D3)") (class "Default")
      (node (ref "TP121") (pin "1") (pinfunction "1_1") (pintype "passive"))
      (node (ref "U2") (pin "BB26") (pinfunction "VTRIM_D3_BB26") (pintype "passive"))
    )
    (net (code "83") (name "Net-(U2E-GPI[0]_D4)") (class "Default")
      (node (ref "TP20") (pin "1") (pinfunction "1_1") (pintype "passive"))
      (node (ref "U2") (pin "BD17") (pinfunction "GPI[0]_D4_BD17") (pintype "passive"))
    )
    (net (code "84") (name "Net-(U2E-GPI[1]_D4)") (class "Default")
      (node (ref "TP88") (pin "1") (pinfunction "1_1") (pintype "passive"))
      (node (ref "U2") (pin "BB17") (pinfunction "GPI[1]_D4_BB17") (pintype "passive"))
    )
    (net (code "85") (name "Net-(U2E-GPI[2]_D4)") (class "Default")
      (node (ref "TP91") (pin "1") (pinfunction "1_1") (pintype "passive"))
      (node (ref "U2") (pin "BD16") (pinfunction "GPI[2]_D4_BD16") (pintype "passive"))
    )
    (net (code "86") (name "Net-(U2E-GPI[3]_D4)") (class "Default")
      (node (ref "TP94") (pin "1") (pinfunction "1_1") (pintype "passive"))
      (node (ref "U2") (pin "BC16") (pinfunction "GPI[3]_D4_BC16") (pintype "passive"))
    )
    (net (code "87") (name "Net-(U2E-GPI[4]_D4)") (class "Default")
      (node (ref "TP33") (pin "1") (pinfunction "1_1") (pintype "passive"))
      (node (ref "U2") (pin "BC15") (pinfunction "GPI[4]_D4_BC15") (pintype "passive"))
    )
    (net (code "88") (name "Net-(U2E-GPI[5]_D4)") (class "Default")
      (node (ref "R47") (pin "1") (pinfunction "1_1") (pintype "passive"))
      (node (ref "U2") (pin "BB15") (pinfunction "GPI[5]_D4_BB15") (pintype "passive"))
    )
    (net (code "89") (name "Net-(U2E-GPI[6]_D4)") (class "Default")
      (node (ref "R49") (pin "1") (pinfunction "1_1") (pintype "passive"))
      (node (ref "U2") (pin "BD14") (pinfunction "GPI[6]_D4_BD14") (pintype "passive"))
    )
    (net (code "90") (name "Net-(U2E-GPI[7]_D4)") (class "Default")
      (node (ref "R48") (pin "1") (pinfunction "1_1") (pintype "passive"))
      (node (ref "U2") (pin "BB14") (pinfunction "GPI[7]_D4_BB14") (pintype "passive"))
    )
    (net (code "91") (name "Net-(U2E-GPO[0]_D4)") (class "Default")
      (node (ref "TP69") (pin "1") (pinfunction "1_1") (pintype "passive"))
      (node (ref "U2") (pin "BD13") (pinfunction "GPO[0]_D4_BD13") (pintype "passive"))
    )
    (net (code "92") (name "Net-(U2E-GPO[1]_D4)") (class "Default")
      (node (ref "TP65") (pin "1") (pinfunction "1_1") (pintype "passive"))
      (node (ref "U2") (pin "BC13") (pinfunction "GPO[1]_D4_BC13") (pintype "passive"))
    )
    (net (code "93") (name "Net-(U2E-GPO[2]_D4)") (class "Default")
      (node (ref "TP61") (pin "1") (pinfunction "1_1") (pintype "passive"))
      (node (ref "U2") (pin "BC12") (pinfunction "GPO[2]_D4_BC12") (pintype "passive"))
    )
    (net (code "94") (name "Net-(U2E-GPO[3]_D4)") (class "Default")
      (node (ref "TP57") (pin "1") (pinfunction "1_1") (pintype "passive"))
      (node (ref "U2") (pin "BD12") (pinfunction "GPO[3]_D4_BD12") (pintype "passive"))
    )
    (net (code "95") (name "Net-(U2E-GPO[4]_D4)") (class "Default")
      (node (ref "TP77") (pin "1") (pinfunction "1_1") (pintype "passive"))
      (node (ref "U2") (pin "BD11") (pinfunction "GPO[4]_D4_BD11") (pintype "passive"))
    )
    (net (code "96") (name "Net-(U2E-GPO[5]_D4)") (class "Default")
      (node (ref "TP85") (pin "1") (pinfunction "1_1") (pintype "passive"))
      (node (ref "U2") (pin "BD10") (pinfunction "GPO[5]_D4_BD10") (pintype "passive"))
    )
    (net (code "97") (name "Net-(U2E-GPO[6]_D4)") (class "Default")
      (node (ref "TP37") (pin "1") (pinfunction "1_1") (pintype "passive"))
      (node (ref "U2") (pin "BC10") (pinfunction "GPO[6]_D4_BC10") (pintype "passive"))
    )
    (net (code "98") (name "Net-(U2E-GPO[7]_D4)") (class "Default")
      (node (ref "TP17") (pin "1") (pinfunction "1_1") (pintype "passive"))
      (node (ref "U2") (pin "BD9") (pinfunction "GPO[7]_D4_BD9") (pintype "passive"))
    )
    (net (code "99") (name "Net-(U2E-MODE_D4)") (class "Default")
      (node (ref "R34") (pin "2") (pinfunction "2_2") (pintype "passive"))
      (node (ref "U2") (pin "BD19") (pinfunction "MODE_D4_BD19") (pintype "passive"))
    )
    (net (code "100") (name "Net-(U2E-VTRIM_D4)") (class "Default")
      (node (ref "TP122") (pin "1") (pinfunction "1_1") (pintype "passive"))
      (node (ref "U2") (pin "BB11") (pinfunction "VTRIM_D4_BB11") (pintype "passive"))
    )
  )
)
